# nand.net
KiCad netlist of a schematic drawn in EAGLE
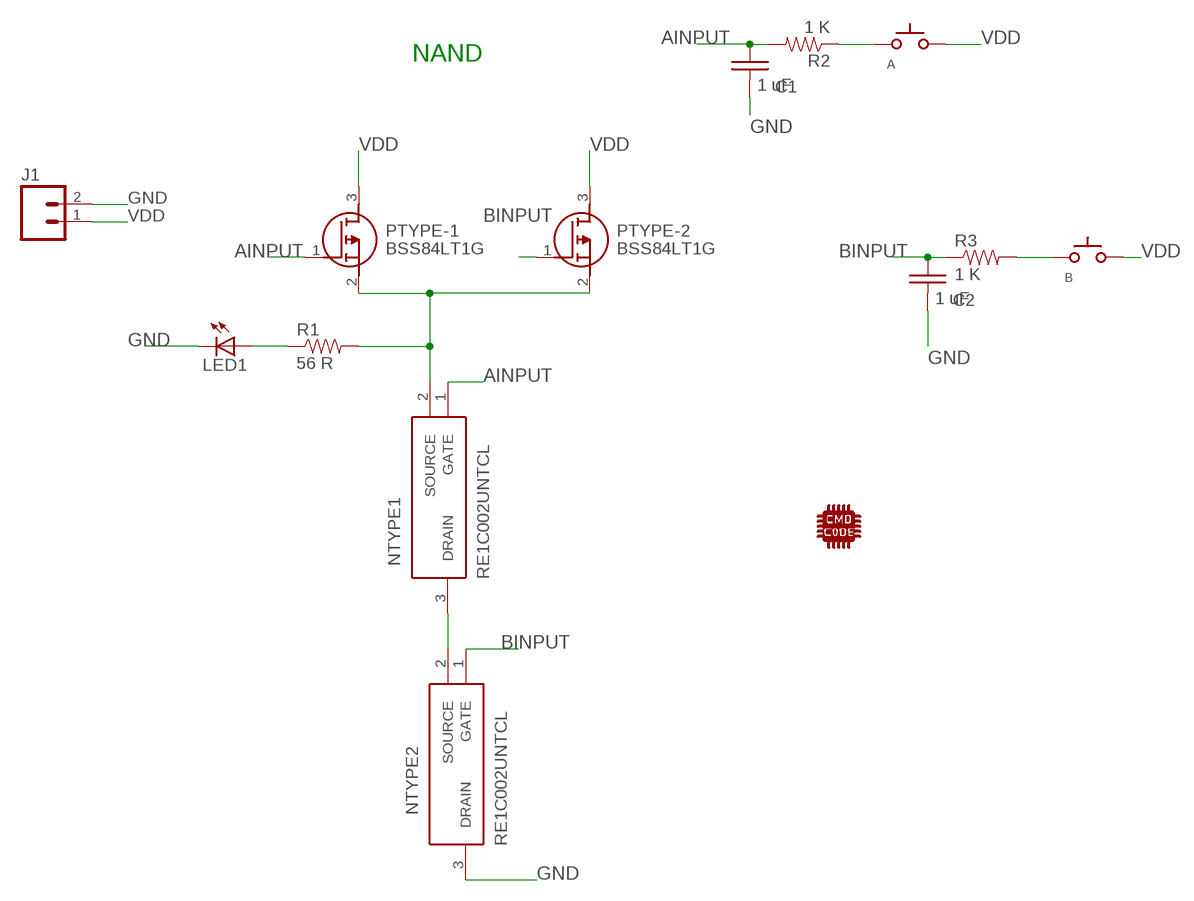
[diagram p0: schematic, sheet 1]

(export (version "E")
  (design (tool "Eeschema 10.0.6"))
  (components
    (comp (ref "A")
      (value "SWITCH_TACTILETACTILE-2PIN-NARROW")
      (footprint "eagle-import:TACTILE-2PIN-NARROW")
      (libsource (lib "eagle-import") (part "SWITCH_TACTILETACTILE-2PIN-NARROW"))
    )
    (comp (ref "B")
      (value "SWITCH_TACTILETACTILE-2PIN-NARROW")
      (footprint "eagle-import:TACTILE-2PIN-NARROW")
      (libsource (lib "eagle-import") (part "SWITCH_TACTILETACTILE-2PIN-NARROW"))
    )
    (comp (ref "C1")
      (value "1 uF")
      (footprint "eagle-import:C1206")
      (libsource (lib "eagle-import") (part "C-USC1206"))
    )
    (comp (ref "C2")
      (value "1 uF")
      (footprint "eagle-import:C1206")
      (libsource (lib "eagle-import") (part "C-USC1206"))
    )
    (comp (ref "J1")
      (value "M021X02_NO_SILK")
      (footprint "eagle-import:1X02_NO_SILK")
      (libsource (lib "eagle-import") (part "M021X02_NO_SILK"))
    )
    (comp (ref "LED1")
      (value "LED3MM")
      (footprint "eagle-import:LED3MM")
      (libsource (lib "eagle-import") (part "LED3MM"))
    )
    (comp (ref "NTYPE1")
      (value "RE1C002UNTCL")
      (footprint "eagle-import:SOT50P160X85-3N")
      (fields (field (name "MOUSER_PART_NUMBER") "755-RE1C002UNTCL"))
      (libsource (lib "eagle-import") (part "RE1C002UNTCL"))
    )
    (comp (ref "NTYPE2")
      (value "RE1C002UNTCL")
      (footprint "eagle-import:SOT50P160X85-3N")
      (fields (field (name "MOUSER_PART_NUMBER") "755-RE1C002UNTCL"))
      (libsource (lib "eagle-import") (part "RE1C002UNTCL"))
    )
    (comp (ref "PTYPE-1")
      (value "BSS84LT1G")
      (footprint "eagle-import:SOT96P237X111-3N")
      (fields (field (name "MOUSER_PART_NUMBER") "863-BSS84LT1G"))
      (libsource (lib "eagle-import") (part "BSS84LT1G"))
    )
    (comp (ref "PTYPE-2")
      (value "BSS84LT1G")
      (footprint "eagle-import:SOT96P237X111-3N")
      (fields (field (name "MOUSER_PART_NUMBER") "863-BSS84LT1G"))
      (libsource (lib "eagle-import") (part "BSS84LT1G"))
    )
    (comp (ref "R1")
      (value "56 R")
      (footprint "eagle-import:1206")
      (libsource (lib "eagle-import") (part "RESISTOR1206"))
    )
    (comp (ref "R2")
      (value "1 K")
      (footprint "eagle-import:0805")
      (libsource (lib "eagle-import") (part "RESISTOR0805-RES"))
    )
    (comp (ref "R3")
      (value "1 K")
      (footprint "eagle-import:0805")
      (libsource (lib "eagle-import") (part "RESISTOR0805-RES"))
    )
    (comp (ref "U$1")
      (value "CMD_C0DE_LOGOCMD_CODE_LOGO_TOP_COPPER")
      (footprint "eagle-import:CMD_C0DE_LOGO_TOP_COPPER")
      (libsource (lib "eagle-import") (part "CMD_C0DE_LOGOCMD_CODE_LOGO_TOP_COPPER"))
    )
  )
  (nets
    (net (code "1") (name "/AINPUT") (class "Default")
      (node (ref "C1") (pin "1") (pinfunction "1_1") (pintype "passive"))
      (node (ref "NTYPE1") (pin "1") (pinfunction "GATE_1") (pintype "bidirectional"))
      (node (ref "PTYPE-1") (pin "1") (pinfunction "G_1") (pintype "bidirectional"))
      (node (ref "R2") (pin "2") (pinfunction "2_2") (pintype "passive"))
    )
    (net (code "2") (name "/BINPUT") (class "Default")
      (node (ref "C2") (pin "1") (pinfunction "1_1") (pintype "passive"))
      (node (ref "NTYPE2") (pin "1") (pinfunction "GATE_1") (pintype "bidirectional"))
      (node (ref "PTYPE-2") (pin "1") (pinfunction "G_1") (pintype "bidirectional"))
      (node (ref "R3") (pin "1") (pinfunction "1_1") (pintype "passive"))
    )
    (net (code "3") (name "/GND") (class "Default")
      (node (ref "C1") (pin "2") (pinfunction "2_2") (pintype "passive"))
      (node (ref "C2") (pin "2") (pinfunction "2_2") (pintype "passive"))
      (node (ref "J1") (pin "2") (pinfunction "2_2") (pintype "passive"))
      (node (ref "LED1") (pin "K") (pinfunction "C_K") (pintype "output"))
      (node (ref "NTYPE2") (pin "3") (pinfunction "DRAIN_3") (pintype "input"))
    )
    (net (code "4") (name "/VDD") (class "Default")
      (node (ref "A") (pin "P$1") (pinfunction "A_P$1") (pintype "passive"))
      (node (ref "B") (pin "P$1") (pinfunction "A_P$1") (pintype "passive"))
      (node (ref "J1") (pin "1") (pinfunction "1_1") (pintype "passive"))
      (node (ref "PTYPE-1") (pin "3") (pinfunction "D_3") (pintype "bidirectional"))
      (node (ref "PTYPE-2") (pin "3") (pinfunction "D_3") (pintype "bidirectional"))
    )
    (net (code "5") (name "Net-(A-C)") (class "Default")
      (node (ref "A") (pin "P$2") (pinfunction "C_P$2") (pintype "passive"))
      (node (ref "R2") (pin "1") (pinfunction "1_1") (pintype "passive"))
    )
    (net (code "6") (name "Net-(B-C)") (class "Default")
      (node (ref "B") (pin "P$2") (pinfunction "C_P$2") (pintype "passive"))
      (node (ref "R3") (pin "2") (pinfunction "2_2") (pintype "passive"))
    )
    (net (code "7") (name "Net-(LED1-PadA)") (class "Default")
      (node (ref "LED1") (pin "A") (pinfunction "A_A") (pintype "input"))
      (node (ref "R1") (pin "1") (pinfunction "1_1") (pintype "passive"))
    )
    (net (code "8") (name "Net-(NTYPE1-DRAIN)") (class "Default")
      (node (ref "NTYPE1") (pin "3") (pinfunction "DRAIN_3") (pintype "input"))
      (node (ref "NTYPE2") (pin "2") (pinfunction "SOURCE_2") (pintype "bidirectional"))
    )
    (net (code "9") (name "Net-(NTYPE1-SOURCE)") (class "Default")
      (node (ref "NTYPE1") (pin "2") (pinfunction "SOURCE_2") (pintype "bidirectional"))
      (node (ref "PTYPE-1") (pin "2") (pinfunction "S_2") (pintype "bidirectional"))
      (node (ref "PTYPE-2") (pin "2") (pinfunction "S_2") (pintype "bidirectional"))
      (node (ref "R1") (pin "2") (pinfunction "2_2") (pintype "passive"))
    )
  )
)
